# BeVimExpansionBoard.net
KiCad netlist of a schematic drawn in EAGLE
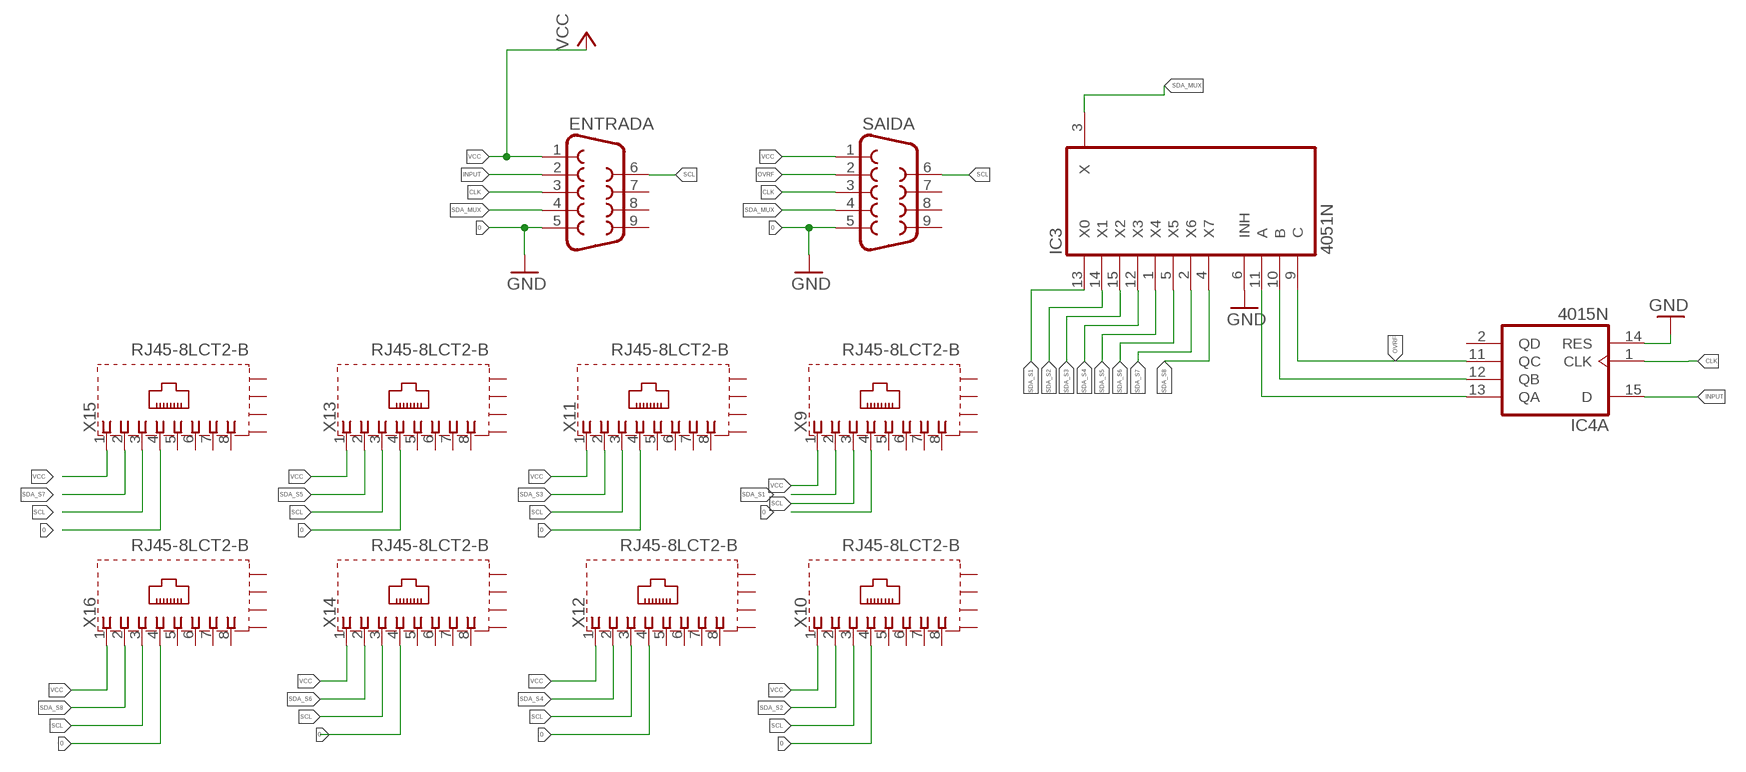
[diagram p0: schematic, sheet 1]

(export (version "E")
  (design (tool "Eeschema 10.0.6"))
  (components
    (comp (ref "ENTRADA")
      (value "DB9FEMALE")
      (footprint "eagle-import:DB9")
      (libsource (lib "eagle-import") (part "DB9FEMALE"))
    )
    (comp (ref "IC3")
      (value "4051N")
      (footprint "eagle-import:DIL16")
      (libsource (lib "eagle-import") (part "4051N"))
    )
    (comp (ref "IC4")
      (value "4015N")
      (footprint "eagle-import:DIL16")
      (libsource (lib "eagle-import") (part "4015N"))
    )
    (comp (ref "SAIDA")
      (value "DB9FEMALE")
      (footprint "eagle-import:DB9")
      (libsource (lib "eagle-import") (part "DB9FEMALE"))
    )
    (comp (ref "X9")
      (value "RJ45-8LCT2-B")
      (footprint "eagle-import:RJ45-SHIELD2")
      (fields (field (name "MF") "TYCO ELECTRONICS"))
      (libsource (lib "eagle-import") (part "RJ452-B-8LCT"))
    )
    (comp (ref "X10")
      (value "RJ45-8LCT2-B")
      (footprint "eagle-import:RJ45-SHIELD2")
      (fields (field (name "MF") "TYCO ELECTRONICS"))
      (libsource (lib "eagle-import") (part "RJ452-B-8LCT"))
    )
    (comp (ref "X11")
      (value "RJ45-8LCT2-B")
      (footprint "eagle-import:RJ45-SHIELD2")
      (fields (field (name "MF") "TYCO ELECTRONICS"))
      (libsource (lib "eagle-import") (part "RJ452-B-8LCT"))
    )
    (comp (ref "X12")
      (value "RJ45-8LCT2-B")
      (footprint "eagle-import:RJ45-SHIELD2")
      (fields (field (name "MF") "TYCO ELECTRONICS"))
      (libsource (lib "eagle-import") (part "RJ452-B-8LCT"))
    )
    (comp (ref "X13")
      (value "RJ45-8LCT2-B")
      (footprint "eagle-import:RJ45-SHIELD2")
      (fields (field (name "MF") "TYCO ELECTRONICS"))
      (libsource (lib "eagle-import") (part "RJ452-B-8LCT"))
    )
    (comp (ref "X14")
      (value "RJ45-8LCT2-B")
      (footprint "eagle-import:RJ45-SHIELD2")
      (fields (field (name "MF") "TYCO ELECTRONICS"))
      (libsource (lib "eagle-import") (part "RJ452-B-8LCT"))
    )
    (comp (ref "X15")
      (value "RJ45-8LCT2-B")
      (footprint "eagle-import:RJ45-SHIELD2")
      (fields (field (name "MF") "TYCO ELECTRONICS"))
      (libsource (lib "eagle-import") (part "RJ452-B-8LCT"))
    )
    (comp (ref "X16")
      (value "RJ45-8LCT2-B")
      (footprint "eagle-import:RJ45-SHIELD2")
      (fields (field (name "MF") "TYCO ELECTRONICS"))
      (libsource (lib "eagle-import") (part "RJ452-B-8LCT"))
    )
  )
  (nets
    (net (code "1") (name "0") (class "Default")
      (node (ref "ENTRADA") (pin "5") (pinfunction "5_5") (pintype "passive"))
      (node (ref "IC3") (pin "6") (pinfunction "INH_6") (pintype "input"))
      (node (ref "IC4") (pin "14") (pinfunction "RES_14") (pintype "input"))
      (node (ref "SAIDA") (pin "5") (pinfunction "5_5") (pintype "passive"))
      (node (ref "X10") (pin "4") (pinfunction "4_4") (pintype "passive"))
      (node (ref "X11") (pin "4") (pinfunction "4_4") (pintype "passive"))
      (node (ref "X12") (pin "4") (pinfunction "4_4") (pintype "passive"))
      (node (ref "X13") (pin "4") (pinfunction "4_4") (pintype "passive"))
      (node (ref "X14") (pin "4") (pinfunction "4_4") (pintype "passive"))
      (node (ref "X15") (pin "4") (pinfunction "4_4") (pintype "passive"))
      (node (ref "X16") (pin "4") (pinfunction "4_4") (pintype "passive"))
      (node (ref "X9") (pin "4") (pinfunction "4_4") (pintype "passive"))
    )
    (net (code "2") (name "CLK") (class "Default")
      (node (ref "ENTRADA") (pin "3") (pinfunction "3_3") (pintype "passive"))
      (node (ref "IC4") (pin "1") (pinfunction "CLK_1") (pintype "input"))
      (node (ref "SAIDA") (pin "3") (pinfunction "3_3") (pintype "passive"))
    )
    (net (code "3") (name "INPUT") (class "Default")
      (node (ref "ENTRADA") (pin "2") (pinfunction "2_2") (pintype "passive"))
      (node (ref "IC4") (pin "15") (pinfunction "D_15") (pintype "input"))
    )
    (net (code "4") (name "Net-(IC3A-A)") (class "Default")
      (node (ref "IC3") (pin "11") (pinfunction "A_11") (pintype "input"))
      (node (ref "IC4") (pin "13") (pinfunction "QA_13") (pintype "output"))
    )
    (net (code "5") (name "Net-(IC3A-B)") (class "Default")
      (node (ref "IC3") (pin "10") (pinfunction "B_10") (pintype "input"))
      (node (ref "IC4") (pin "12") (pinfunction "QB_12") (pintype "output"))
    )
    (net (code "6") (name "OVRF") (class "Default")
      (node (ref "IC3") (pin "9") (pinfunction "C_9") (pintype "input"))
      (node (ref "IC4") (pin "11") (pinfunction "QC_11") (pintype "output"))
      (node (ref "SAIDA") (pin "2") (pinfunction "2_2") (pintype "passive"))
    )
    (net (code "7") (name "SCL") (class "Default")
      (node (ref "ENTRADA") (pin "6") (pinfunction "6_6") (pintype "passive"))
      (node (ref "SAIDA") (pin "6") (pinfunction "6_6") (pintype "passive"))
      (node (ref "X10") (pin "3") (pinfunction "3_3") (pintype "passive"))
      (node (ref "X11") (pin "3") (pinfunction "3_3") (pintype "passive"))
      (node (ref "X12") (pin "3") (pinfunction "3_3") (pintype "passive"))
      (node (ref "X13") (pin "3") (pinfunction "3_3") (pintype "passive"))
      (node (ref "X14") (pin "3") (pinfunction "3_3") (pintype "passive"))
      (node (ref "X15") (pin "3") (pinfunction "3_3") (pintype "passive"))
      (node (ref "X16") (pin "3") (pinfunction "3_3") (pintype "passive"))
      (node (ref "X9") (pin "3") (pinfunction "3_3") (pintype "passive"))
    )
    (net (code "8") (name "SDA_MUX") (class "Default")
      (node (ref "ENTRADA") (pin "4") (pinfunction "4_4") (pintype "passive"))
      (node (ref "IC3") (pin "3") (pinfunction "X_3") (pintype "bidirectional"))
      (node (ref "SAIDA") (pin "4") (pinfunction "4_4") (pintype "passive"))
    )
    (net (code "9") (name "SDA_S1") (class "Default")
      (node (ref "IC3") (pin "13") (pinfunction "X0_13") (pintype "bidirectional"))
      (node (ref "X9") (pin "2") (pinfunction "2_2") (pintype "passive"))
    )
    (net (code "10") (name "SDA_S2") (class "Default")
      (node (ref "IC3") (pin "14") (pinfunction "X1_14") (pintype "bidirectional"))
      (node (ref "X10") (pin "2") (pinfunction "2_2") (pintype "passive"))
    )
    (net (code "11") (name "SDA_S3") (class "Default")
      (node (ref "IC3") (pin "15") (pinfunction "X2_15") (pintype "bidirectional"))
      (node (ref "X11") (pin "2") (pinfunction "2_2") (pintype "passive"))
    )
    (net (code "12") (name "SDA_S4") (class "Default")
      (node (ref "IC3") (pin "12") (pinfunction "X3_12") (pintype "bidirectional"))
      (node (ref "X12") (pin "2") (pinfunction "2_2") (pintype "passive"))
    )
    (net (code "13") (name "SDA_S5") (class "Default")
      (node (ref "IC3") (pin "1") (pinfunction "X4_1") (pintype "bidirectional"))
      (node (ref "X13") (pin "2") (pinfunction "2_2") (pintype "passive"))
    )
    (net (code "14") (name "SDA_S6") (class "Default")
      (node (ref "IC3") (pin "5") (pinfunction "X5_5") (pintype "bidirectional"))
      (node (ref "X14") (pin "2") (pinfunction "2_2") (pintype "passive"))
    )
    (net (code "15") (name "SDA_S7") (class "Default")
      (node (ref "IC3") (pin "2") (pinfunction "X6_2") (pintype "bidirectional"))
      (node (ref "X15") (pin "2") (pinfunction "2_2") (pintype "passive"))
    )
    (net (code "16") (name "SDA_S8") (class "Default")
      (node (ref "IC3") (pin "4") (pinfunction "X7_4") (pintype "bidirectional"))
      (node (ref "X16") (pin "2") (pinfunction "2_2") (pintype "passive"))
    )
    (net (code "17") (name "VCC") (class "Default")
      (node (ref "ENTRADA") (pin "1") (pinfunction "1_1") (pintype "passive"))
      (node (ref "SAIDA") (pin "1") (pinfunction "1_1") (pintype "passive"))
      (node (ref "X10") (pin "1") (pinfunction "1_1") (pintype "passive"))
      (node (ref "X11") (pin "1") (pinfunction "1_1") (pintype "passive"))
      (node (ref "X12") (pin "1") (pinfunction "1_1") (pintype "passive"))
      (node (ref "X13") (pin "1") (pinfunction "1_1") (pintype "passive"))
      (node (ref "X14") (pin "1") (pinfunction "1_1") (pintype "passive"))
      (node (ref "X15") (pin "1") (pinfunction "1_1") (pintype "passive"))
      (node (ref "X16") (pin "1") (pinfunction "1_1") (pintype "passive"))
      (node (ref "X9") (pin "1") (pinfunction "1_1") (pintype "passive"))
    )
    (net (code "18") (name "unconnected-(ENTRADA-Pad7)") (class "Default")
      (node (ref "ENTRADA") (pin "7") (pinfunction "7_7") (pintype "passive"))
    )
    (net (code "19") (name "unconnected-(ENTRADA-Pad8)") (class "Default")
      (node (ref "ENTRADA") (pin "8") (pinfunction "8_8") (pintype "passive"))
    )
    (net (code "20") (name "unconnected-(ENTRADA-Pad9)") (class "Default")
      (node (ref "ENTRADA") (pin "9") (pinfunction "9_9") (pintype "passive"))
    )
    (net (code "21") (name "unconnected-(IC4A-QD-Pad2)") (class "Default")
      (node (ref "IC4") (pin "2") (pinfunction "QD_2") (pintype "output"))
    )
    (net (code "22") (name "unconnected-(SAIDA-Pad7)") (class "Default")
      (node (ref "SAIDA") (pin "7") (pinfunction "7_7") (pintype "passive"))
    )
    (net (code "23") (name "unconnected-(SAIDA-Pad8)") (class "Default")
      (node (ref "SAIDA") (pin "8") (pinfunction "8_8") (pintype "passive"))
    )
    (net (code "24") (name "unconnected-(SAIDA-Pad9)") (class "Default")
      (node (ref "SAIDA") (pin "9") (pinfunction "9_9") (pintype "passive"))
    )
    (net (code "25") (name "unconnected-(X9-Pad5)") (class "Default")
      (node (ref "X9") (pin "5") (pinfunction "5_5") (pintype "passive"))
    )
    (net (code "26") (name "unconnected-(X9-Pad6)") (class "Default")
      (node (ref "X9") (pin "6") (pinfunction "6_6") (pintype "passive"))
    )
    (net (code "27") (name "unconnected-(X9-Pad7)") (class "Default")
      (node (ref "X9") (pin "7") (pinfunction "7_7") (pintype "passive"))
    )
    (net (code "28") (name "unconnected-(X9-Pad8)") (class "Default")
      (node (ref "X9") (pin "8") (pinfunction "8_8") (pintype "passive"))
    )
    (net (code "29") (name "unconnected-(X9-S-PadS1)") (class "Default")
      (node (ref "X9") (pin "S1") (pinfunction "S_S1") (pintype "passive"))
    )
    (net (code "30") (name "unconnected-(X9-S-PadS2)") (class "Default")
      (node (ref "X9") (pin "S2") (pinfunction "S_S2") (pintype "passive"))
    )
    (net (code "31") (name "unconnected-(X9-S-PadS3)") (class "Default")
      (node (ref "X9") (pin "S3") (pinfunction "S_S3") (pintype "passive"))
    )
    (net (code "32") (name "unconnected-(X9-S-PadS4)") (class "Default")
      (node (ref "X9") (pin "S4") (pinfunction "S_S4") (pintype "passive"))
    )
    (net (code "33") (name "unconnected-(X10-Pad5)") (class "Default")
      (node (ref "X10") (pin "5") (pinfunction "5_5") (pintype "passive"))
    )
    (net (code "34") (name "unconnected-(X10-Pad6)") (class "Default")
      (node (ref "X10") (pin "6") (pinfunction "6_6") (pintype "passive"))
    )
    (net (code "35") (name "unconnected-(X10-Pad7)") (class "Default")
      (node (ref "X10") (pin "7") (pinfunction "7_7") (pintype "passive"))
    )
    (net (code "36") (name "unconnected-(X10-Pad8)") (class "Default")
      (node (ref "X10") (pin "8") (pinfunction "8_8") (pintype "passive"))
    )
    (net (code "37") (name "unconnected-(X10-S-PadS1)") (class "Default")
      (node (ref "X10") (pin "S1") (pinfunction "S_S1") (pintype "passive"))
    )
    (net (code "38") (name "unconnected-(X10-S-PadS2)") (class "Default")
      (node (ref "X10") (pin "S2") (pinfunction "S_S2") (pintype "passive"))
    )
    (net (code "39") (name "unconnected-(X10-S-PadS3)") (class "Default")
      (node (ref "X10") (pin "S3") (pinfunction "S_S3") (pintype "passive"))
    )
    (net (code "40") (name "unconnected-(X10-S-PadS4)") (class "Default")
      (node (ref "X10") (pin "S4") (pinfunction "S_S4") (pintype "passive"))
    )
    (net (code "41") (name "unconnected-(X11-Pad5)") (class "Default")
      (node (ref "X11") (pin "5") (pinfunction "5_5") (pintype "passive"))
    )
    (net (code "42") (name "unconnected-(X11-Pad6)") (class "Default")
      (node (ref "X11") (pin "6") (pinfunction "6_6") (pintype "passive"))
    )
    (net (code "43") (name "unconnected-(X11-Pad7)") (class "Default")
      (node (ref "X11") (pin "7") (pinfunction "7_7") (pintype "passive"))
    )
    (net (code "44") (name "unconnected-(X11-Pad8)") (class "Default")
      (node (ref "X11") (pin "8") (pinfunction "8_8") (pintype "passive"))
    )
    (net (code "45") (name "unconnected-(X11-S-PadS1)") (class "Default")
      (node (ref "X11") (pin "S1") (pinfunction "S_S1") (pintype "passive"))
    )
    (net (code "46") (name "unconnected-(X11-S-PadS2)") (class "Default")
      (node (ref "X11") (pin "S2") (pinfunction "S_S2") (pintype "passive"))
    )
    (net (code "47") (name "unconnected-(X11-S-PadS3)") (class "Default")
      (node (ref "X11") (pin "S3") (pinfunction "S_S3") (pintype "passive"))
    )
    (net (code "48") (name "unconnected-(X11-S-PadS4)") (class "Default")
      (node (ref "X11") (pin "S4") (pinfunction "S_S4") (pintype "passive"))
    )
    (net (code "49") (name "unconnected-(X12-Pad5)") (class "Default")
      (node (ref "X12") (pin "5") (pinfunction "5_5") (pintype "passive"))
    )
    (net (code "50") (name "unconnected-(X12-Pad6)") (class "Default")
      (node (ref "X12") (pin "6") (pinfunction "6_6") (pintype "passive"))
    )
    (net (code "51") (name "unconnected-(X12-Pad7)") (class "Default")
      (node (ref "X12") (pin "7") (pinfunction "7_7") (pintype "passive"))
    )
    (net (code "52") (name "unconnected-(X12-Pad8)") (class "Default")
      (node (ref "X12") (pin "8") (pinfunction "8_8") (pintype "passive"))
    )
    (net (code "53") (name "unconnected-(X12-S-PadS1)") (class "Default")
      (node (ref "X12") (pin "S1") (pinfunction "S_S1") (pintype "passive"))
    )
    (net (code "54") (name "unconnected-(X12-S-PadS2)") (class "Default")
      (node (ref "X12") (pin "S2") (pinfunction "S_S2") (pintype "passive"))
    )
    (net (code "55") (name "unconnected-(X12-S-PadS3)") (class "Default")
      (node (ref "X12") (pin "S3") (pinfunction "S_S3") (pintype "passive"))
    )
    (net (code "56") (name "unconnected-(X12-S-PadS4)") (class "Default")
      (node (ref "X12") (pin "S4") (pinfunction "S_S4") (pintype "passive"))
    )
    (net (code "57") (name "unconnected-(X13-Pad5)") (class "Default")
      (node (ref "X13") (pin "5") (pinfunction "5_5") (pintype "passive"))
    )
    (net (code "58") (name "unconnected-(X13-Pad6)") (class "Default")
      (node (ref "X13") (pin "6") (pinfunction "6_6") (pintype "passive"))
    )
    (net (code "59") (name "unconnected-(X13-Pad7)") (class "Default")
      (node (ref "X13") (pin "7") (pinfunction "7_7") (pintype "passive"))
    )
    (net (code "60") (name "unconnected-(X13-Pad8)") (class "Default")
      (node (ref "X13") (pin "8") (pinfunction "8_8") (pintype "passive"))
    )
    (net (code "61") (name "unconnected-(X13-S-PadS1)") (class "Default")
      (node (ref "X13") (pin "S1") (pinfunction "S_S1") (pintype "passive"))
    )
    (net (code "62") (name "unconnected-(X13-S-PadS2)") (class "Default")
      (node (ref "X13") (pin "S2") (pinfunction "S_S2") (pintype "passive"))
    )
    (net (code "63") (name "unconnected-(X13-S-PadS3)") (class "Default")
      (node (ref "X13") (pin "S3") (pinfunction "S_S3") (pintype "passive"))
    )
    (net (code "64") (name "unconnected-(X13-S-PadS4)") (class "Default")
      (node (ref "X13") (pin "S4") (pinfunction "S_S4") (pintype "passive"))
    )
    (net (code "65") (name "unconnected-(X14-Pad5)") (class "Default")
      (node (ref "X14") (pin "5") (pinfunction "5_5") (pintype "passive"))
    )
    (net (code "66") (name "unconnected-(X14-Pad6)") (class "Default")
      (node (ref "X14") (pin "6") (pinfunction "6_6") (pintype "passive"))
    )
    (net (code "67") (name "unconnected-(X14-Pad7)") (class "Default")
      (node (ref "X14") (pin "7") (pinfunction "7_7") (pintype "passive"))
    )
    (net (code "68") (name "unconnected-(X14-Pad8)") (class "Default")
      (node (ref "X14") (pin "8") (pinfunction "8_8") (pintype "passive"))
    )
    (net (code "69") (name "unconnected-(X14-S-PadS1)") (class "Default")
      (node (ref "X14") (pin "S1") (pinfunction "S_S1") (pintype "passive"))
    )
    (net (code "70") (name "unconnected-(X14-S-PadS2)") (class "Default")
      (node (ref "X14") (pin "S2") (pinfunction "S_S2") (pintype "passive"))
    )
    (net (code "71") (name "unconnected-(X14-S-PadS3)") (class "Default")
      (node (ref "X14") (pin "S3") (pinfunction "S_S3") (pintype "passive"))
    )
    (net (code "72") (name "unconnected-(X14-S-PadS4)") (class "Default")
      (node (ref "X14") (pin "S4") (pinfunction "S_S4") (pintype "passive"))
    )
    (net (code "73") (name "unconnected-(X15-Pad5)") (class "Default")
      (node (ref "X15") (pin "5") (pinfunction "5_5") (pintype "passive"))
    )
    (net (code "74") (name "unconnected-(X15-Pad6)") (class "Default")
      (node (ref "X15") (pin "6") (pinfunction "6_6") (pintype "passive"))
    )
    (net (code "75") (name "unconnected-(X15-Pad7)") (class "Default")
      (node (ref "X15") (pin "7") (pinfunction "7_7") (pintype "passive"))
    )
    (net (code "76") (name "unconnected-(X15-Pad8)") (class "Default")
      (node (ref "X15") (pin "8") (pinfunction "8_8") (pintype "passive"))
    )
    (net (code "77") (name "unconnected-(X15-S-PadS1)") (class "Default")
      (node (ref "X15") (pin "S1") (pinfunction "S_S1") (pintype "passive"))
    )
    (net (code "78") (name "unconnected-(X15-S-PadS2)") (class "Default")
      (node (ref "X15") (pin "S2") (pinfunction "S_S2") (pintype "passive"))
    )
    (net (code "79") (name "unconnected-(X15-S-PadS3)") (class "Default")
      (node (ref "X15") (pin "S3") (pinfunction "S_S3") (pintype "passive"))
    )
    (net (code "80") (name "unconnected-(X15-S-PadS4)") (class "Default")
      (node (ref "X15") (pin "S4") (pinfunction "S_S4") (pintype "passive"))
    )
    (net (code "81") (name "unconnected-(X16-Pad5)") (class "Default")
      (node (ref "X16") (pin "5") (pinfunction "5_5") (pintype "passive"))
    )
    (net (code "82") (name "unconnected-(X16-Pad6)") (class "Default")
      (node (ref "X16") (pin "6") (pinfunction "6_6") (pintype "passive"))
    )
    (net (code "83") (name "unconnected-(X16-Pad7)") (class "Default")
      (node (ref "X16") (pin "7") (pinfunction "7_7") (pintype "passive"))
    )
    (net (code "84") (name "unconnected-(X16-Pad8)") (class "Default")
      (node (ref "X16") (pin "8") (pinfunction "8_8") (pintype "passive"))
    )
    (net (code "85") (name "unconnected-(X16-S-PadS1)") (class "Default")
      (node (ref "X16") (pin "S1") (pinfunction "S_S1") (pintype "passive"))
    )
    (net (code "86") (name "unconnected-(X16-S-PadS2)") (class "Default")
      (node (ref "X16") (pin "S2") (pinfunction "S_S2") (pintype "passive"))
    )
    (net (code "87") (name "unconnected-(X16-S-PadS3)") (class "Default")
      (node (ref "X16") (pin "S3") (pinfunction "S_S3") (pintype "passive"))
    )
    (net (code "88") (name "unconnected-(X16-S-PadS4)") (class "Default")
      (node (ref "X16") (pin "S4") (pinfunction "S_S4") (pintype "passive"))
    )
  )
)
